# msq-dbw.net
KiCad netlist of a schematic drawn in EasyEDA Pro
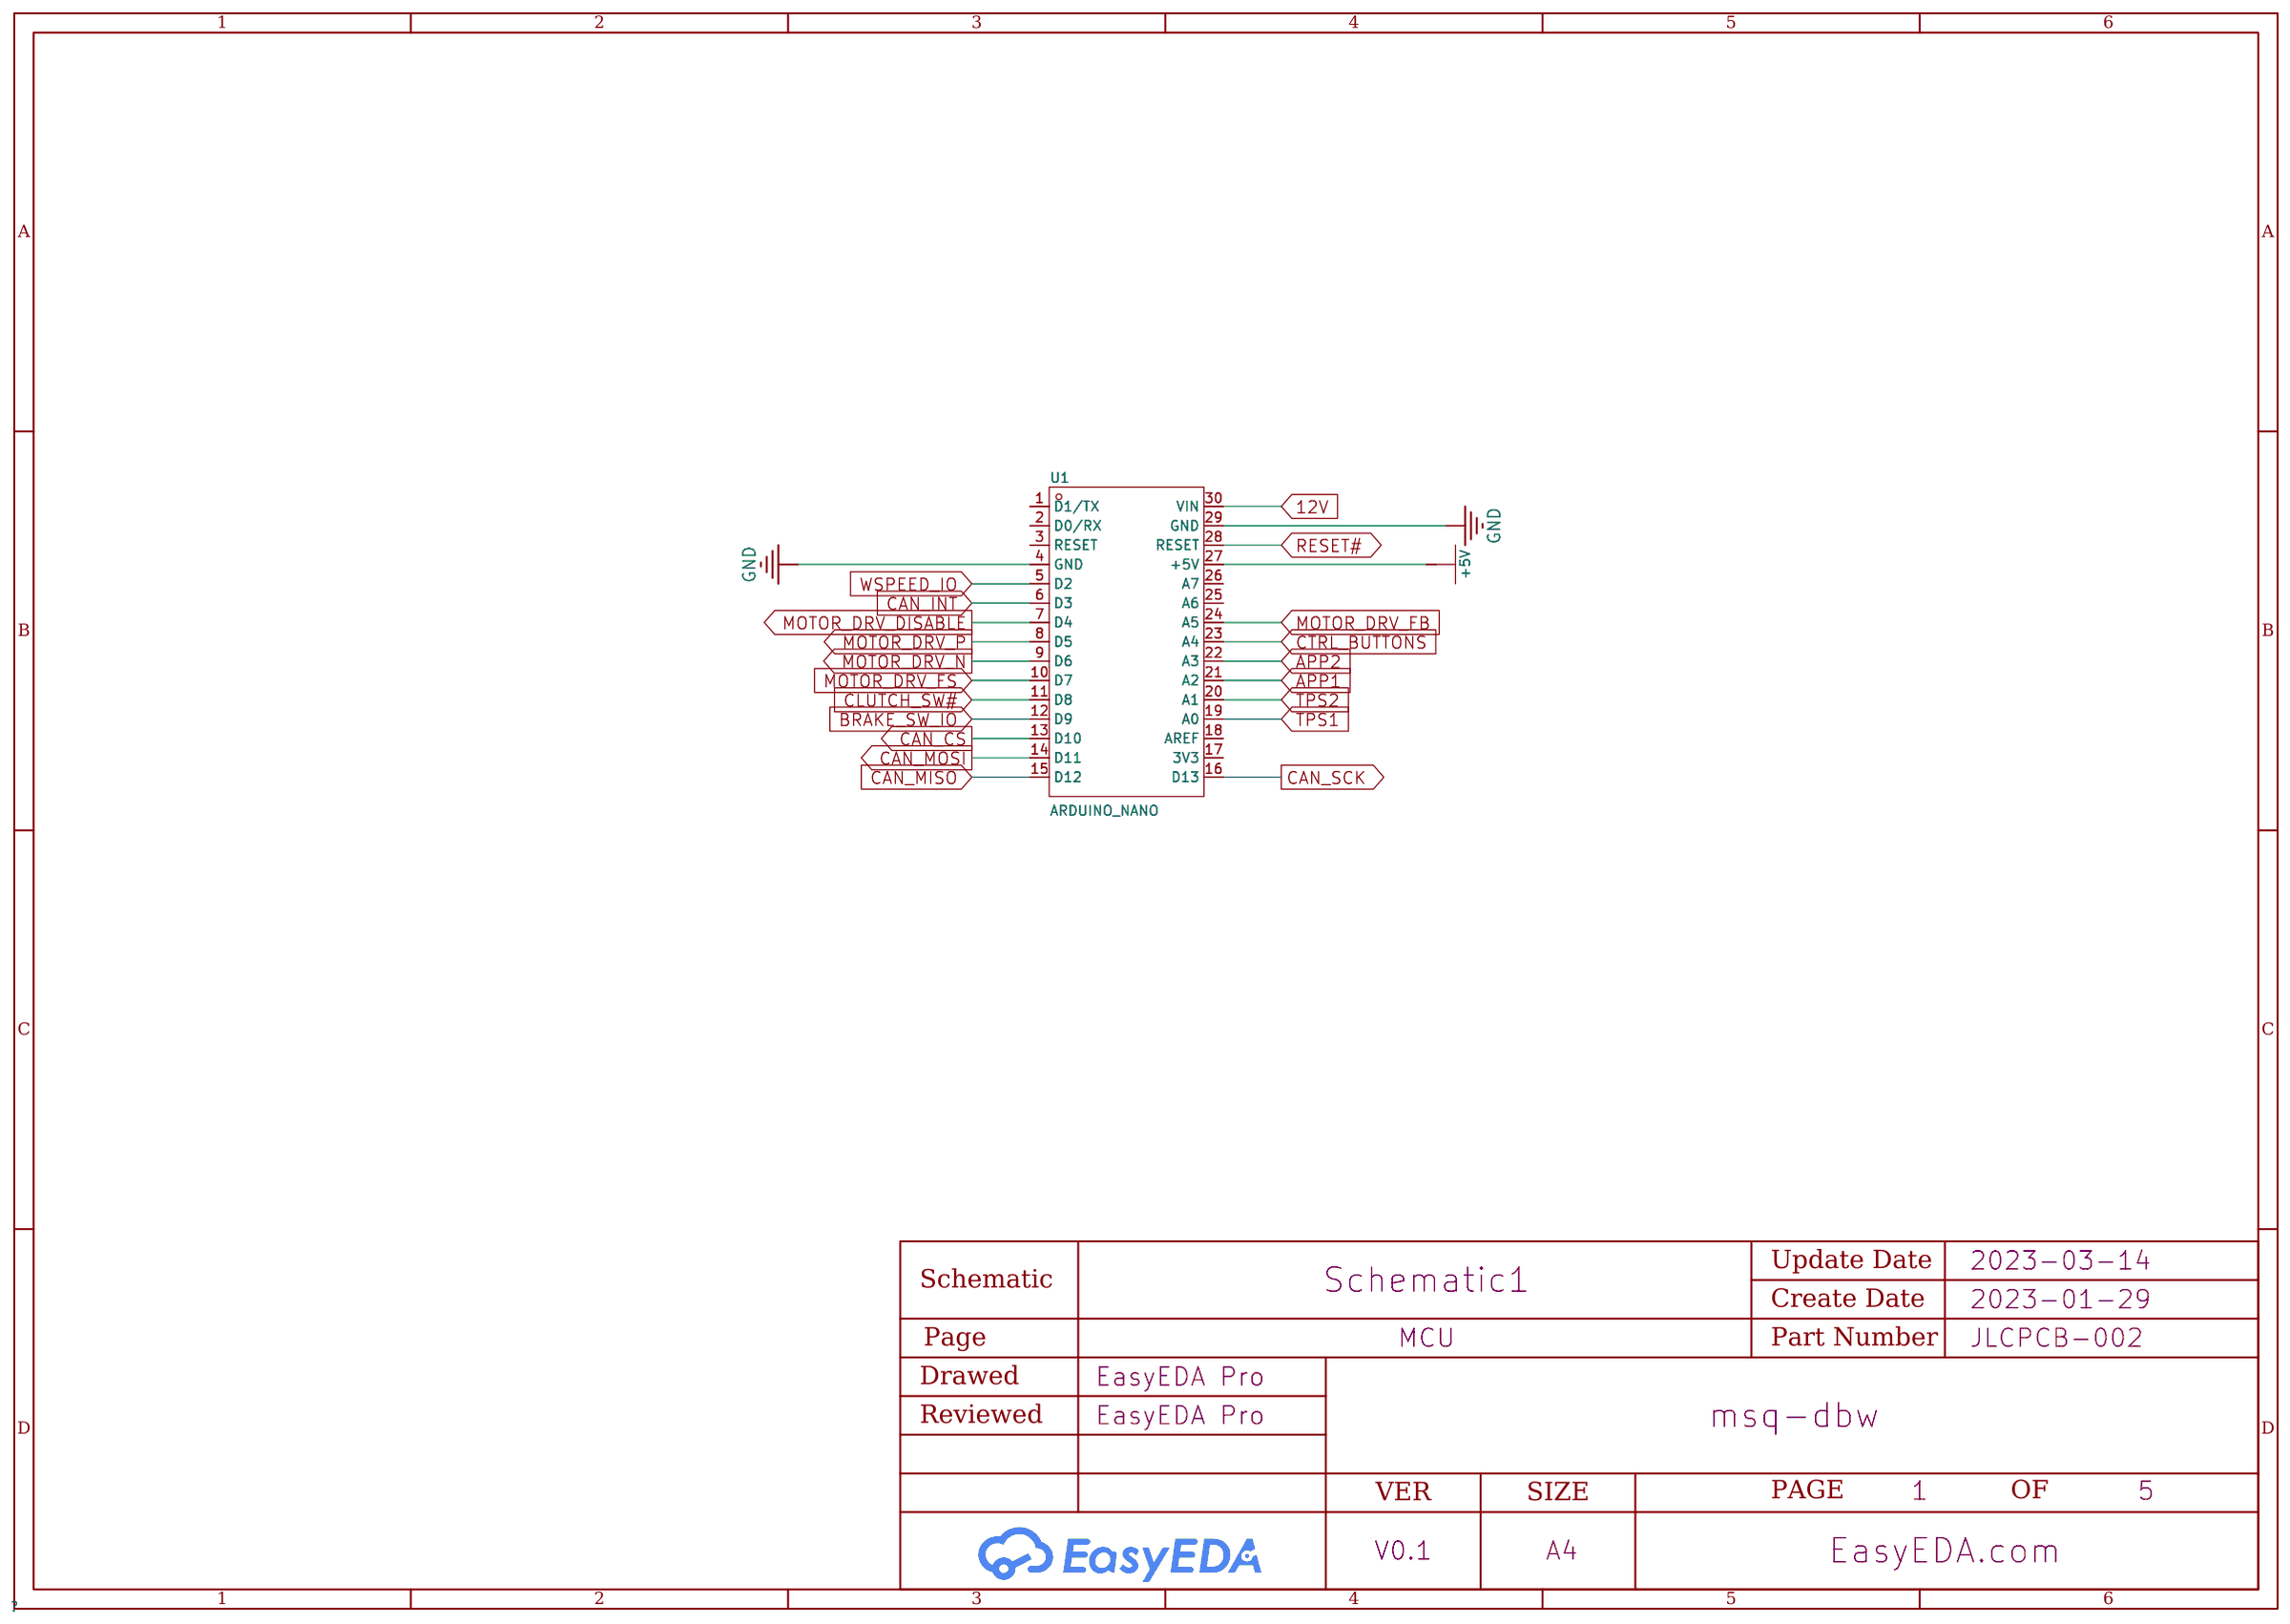
[diagram p0: MCU]
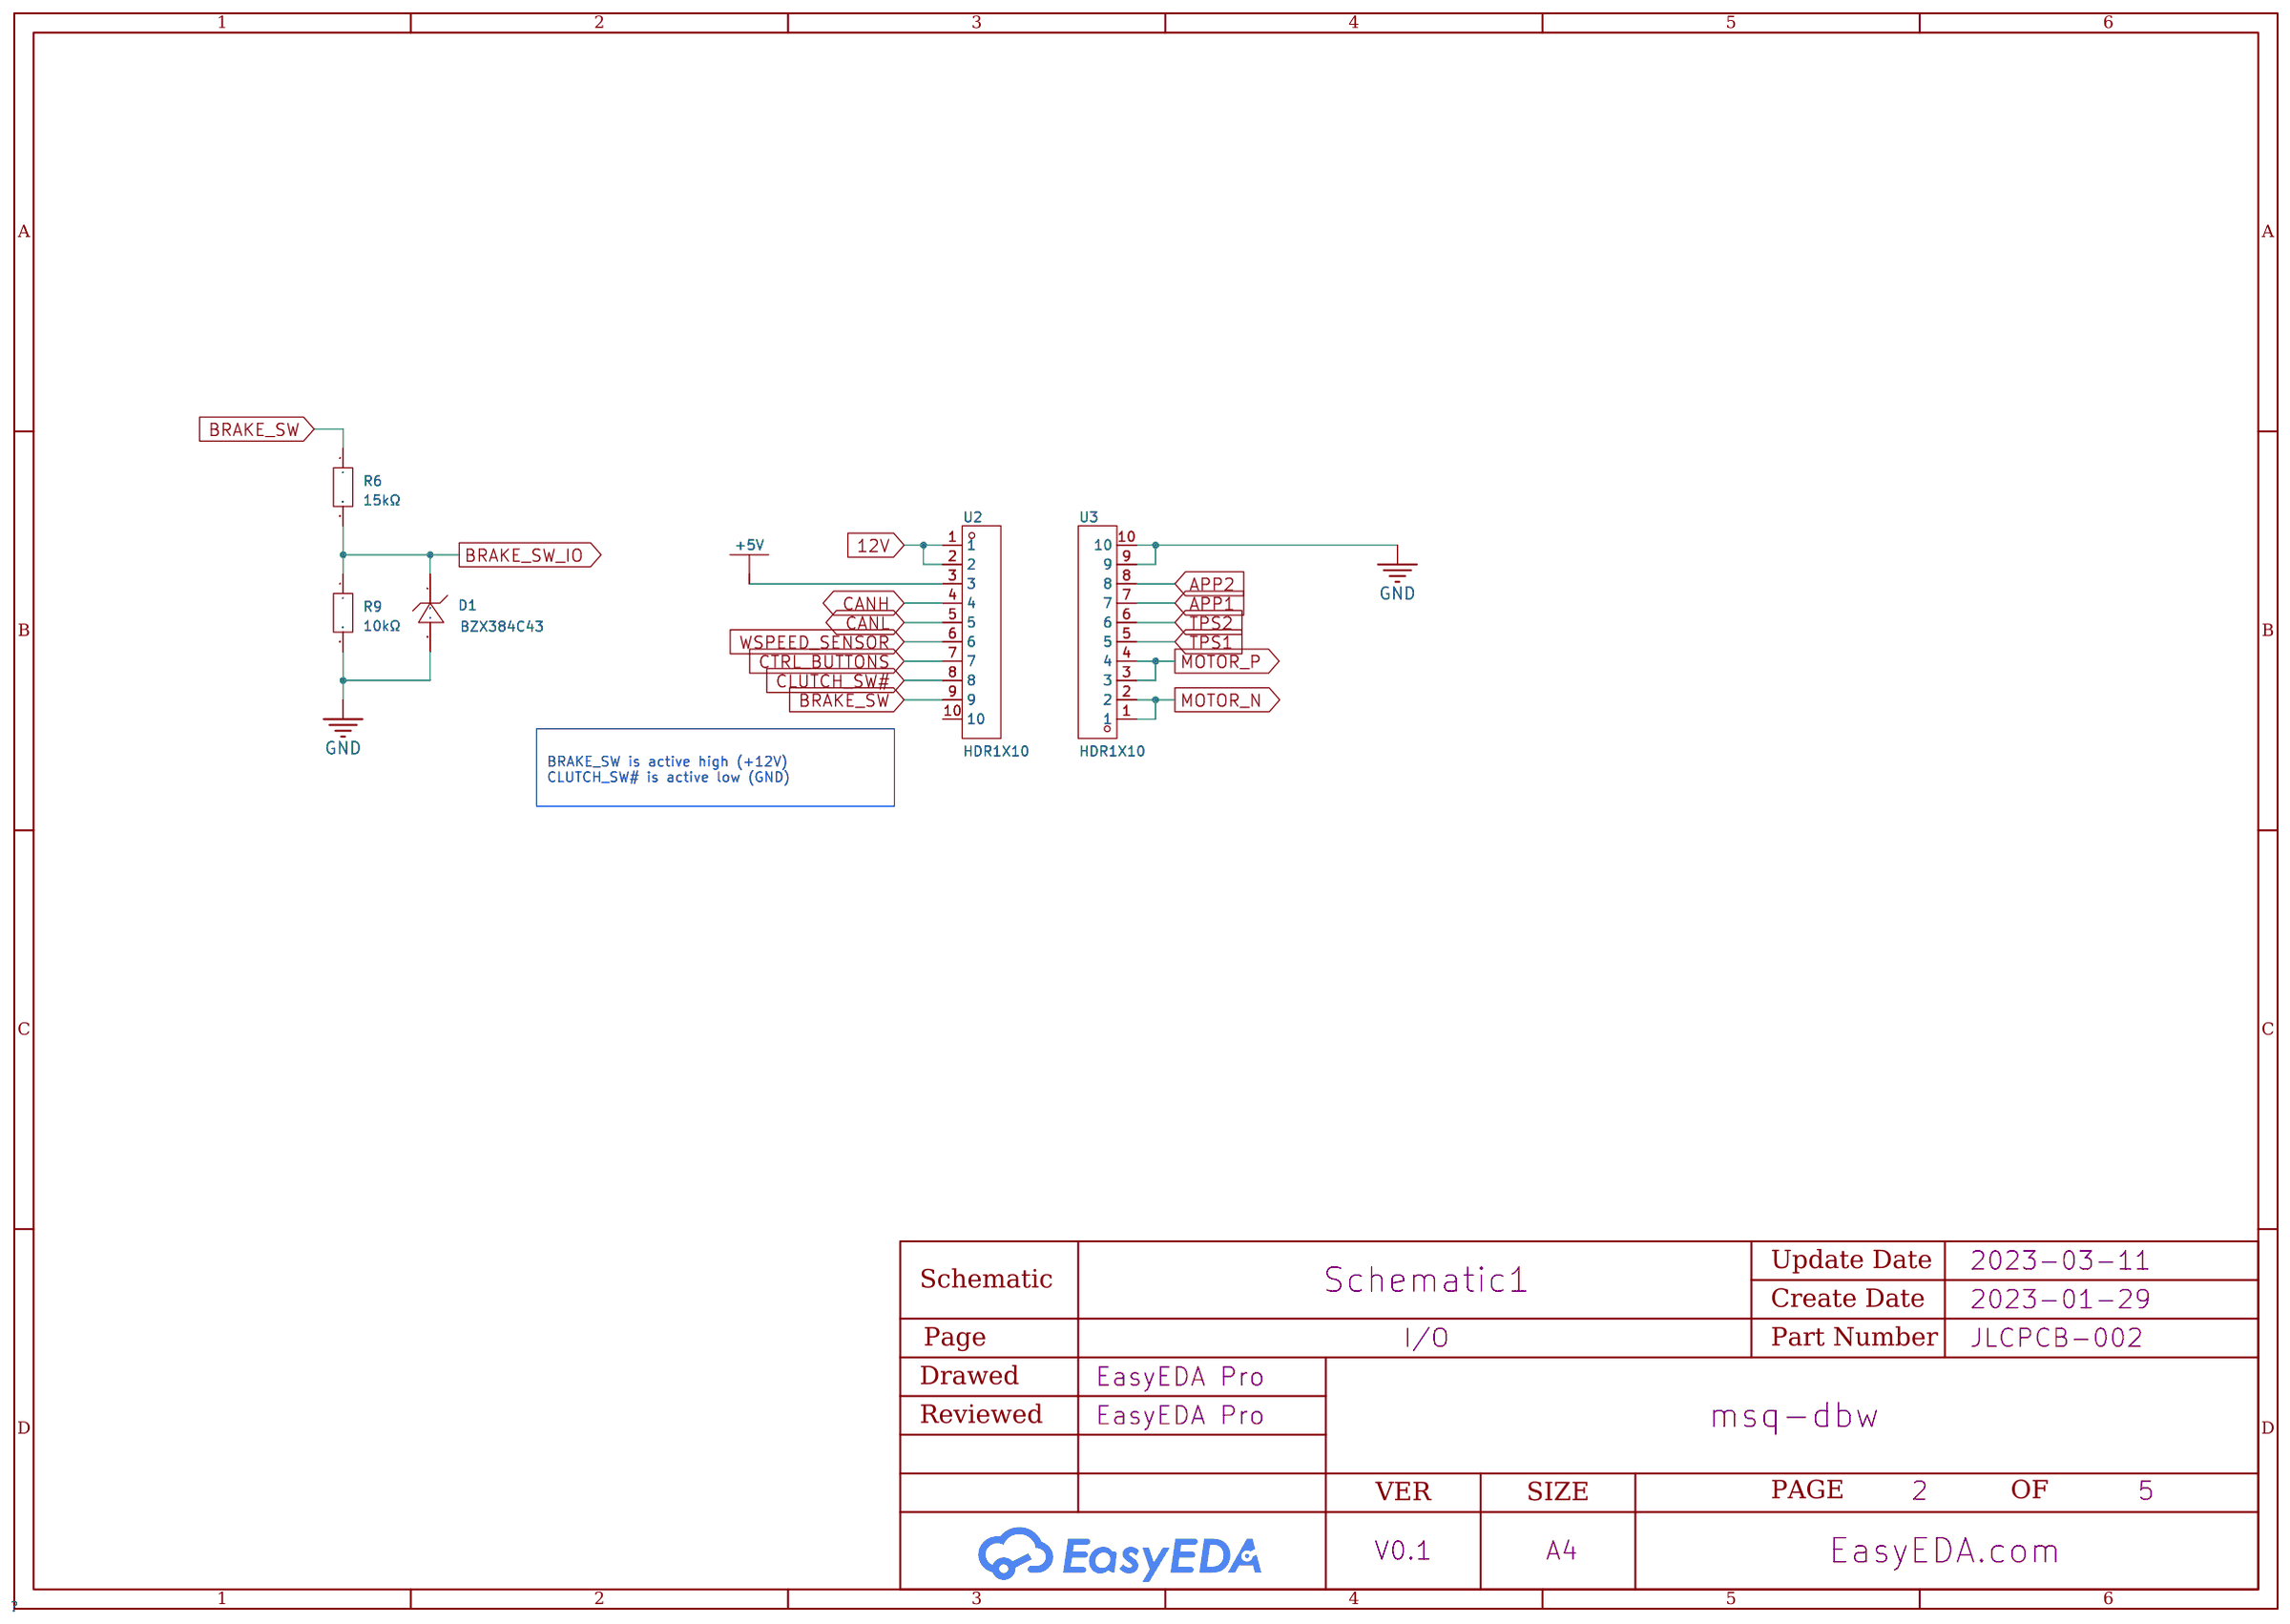
[diagram p1: I/O]
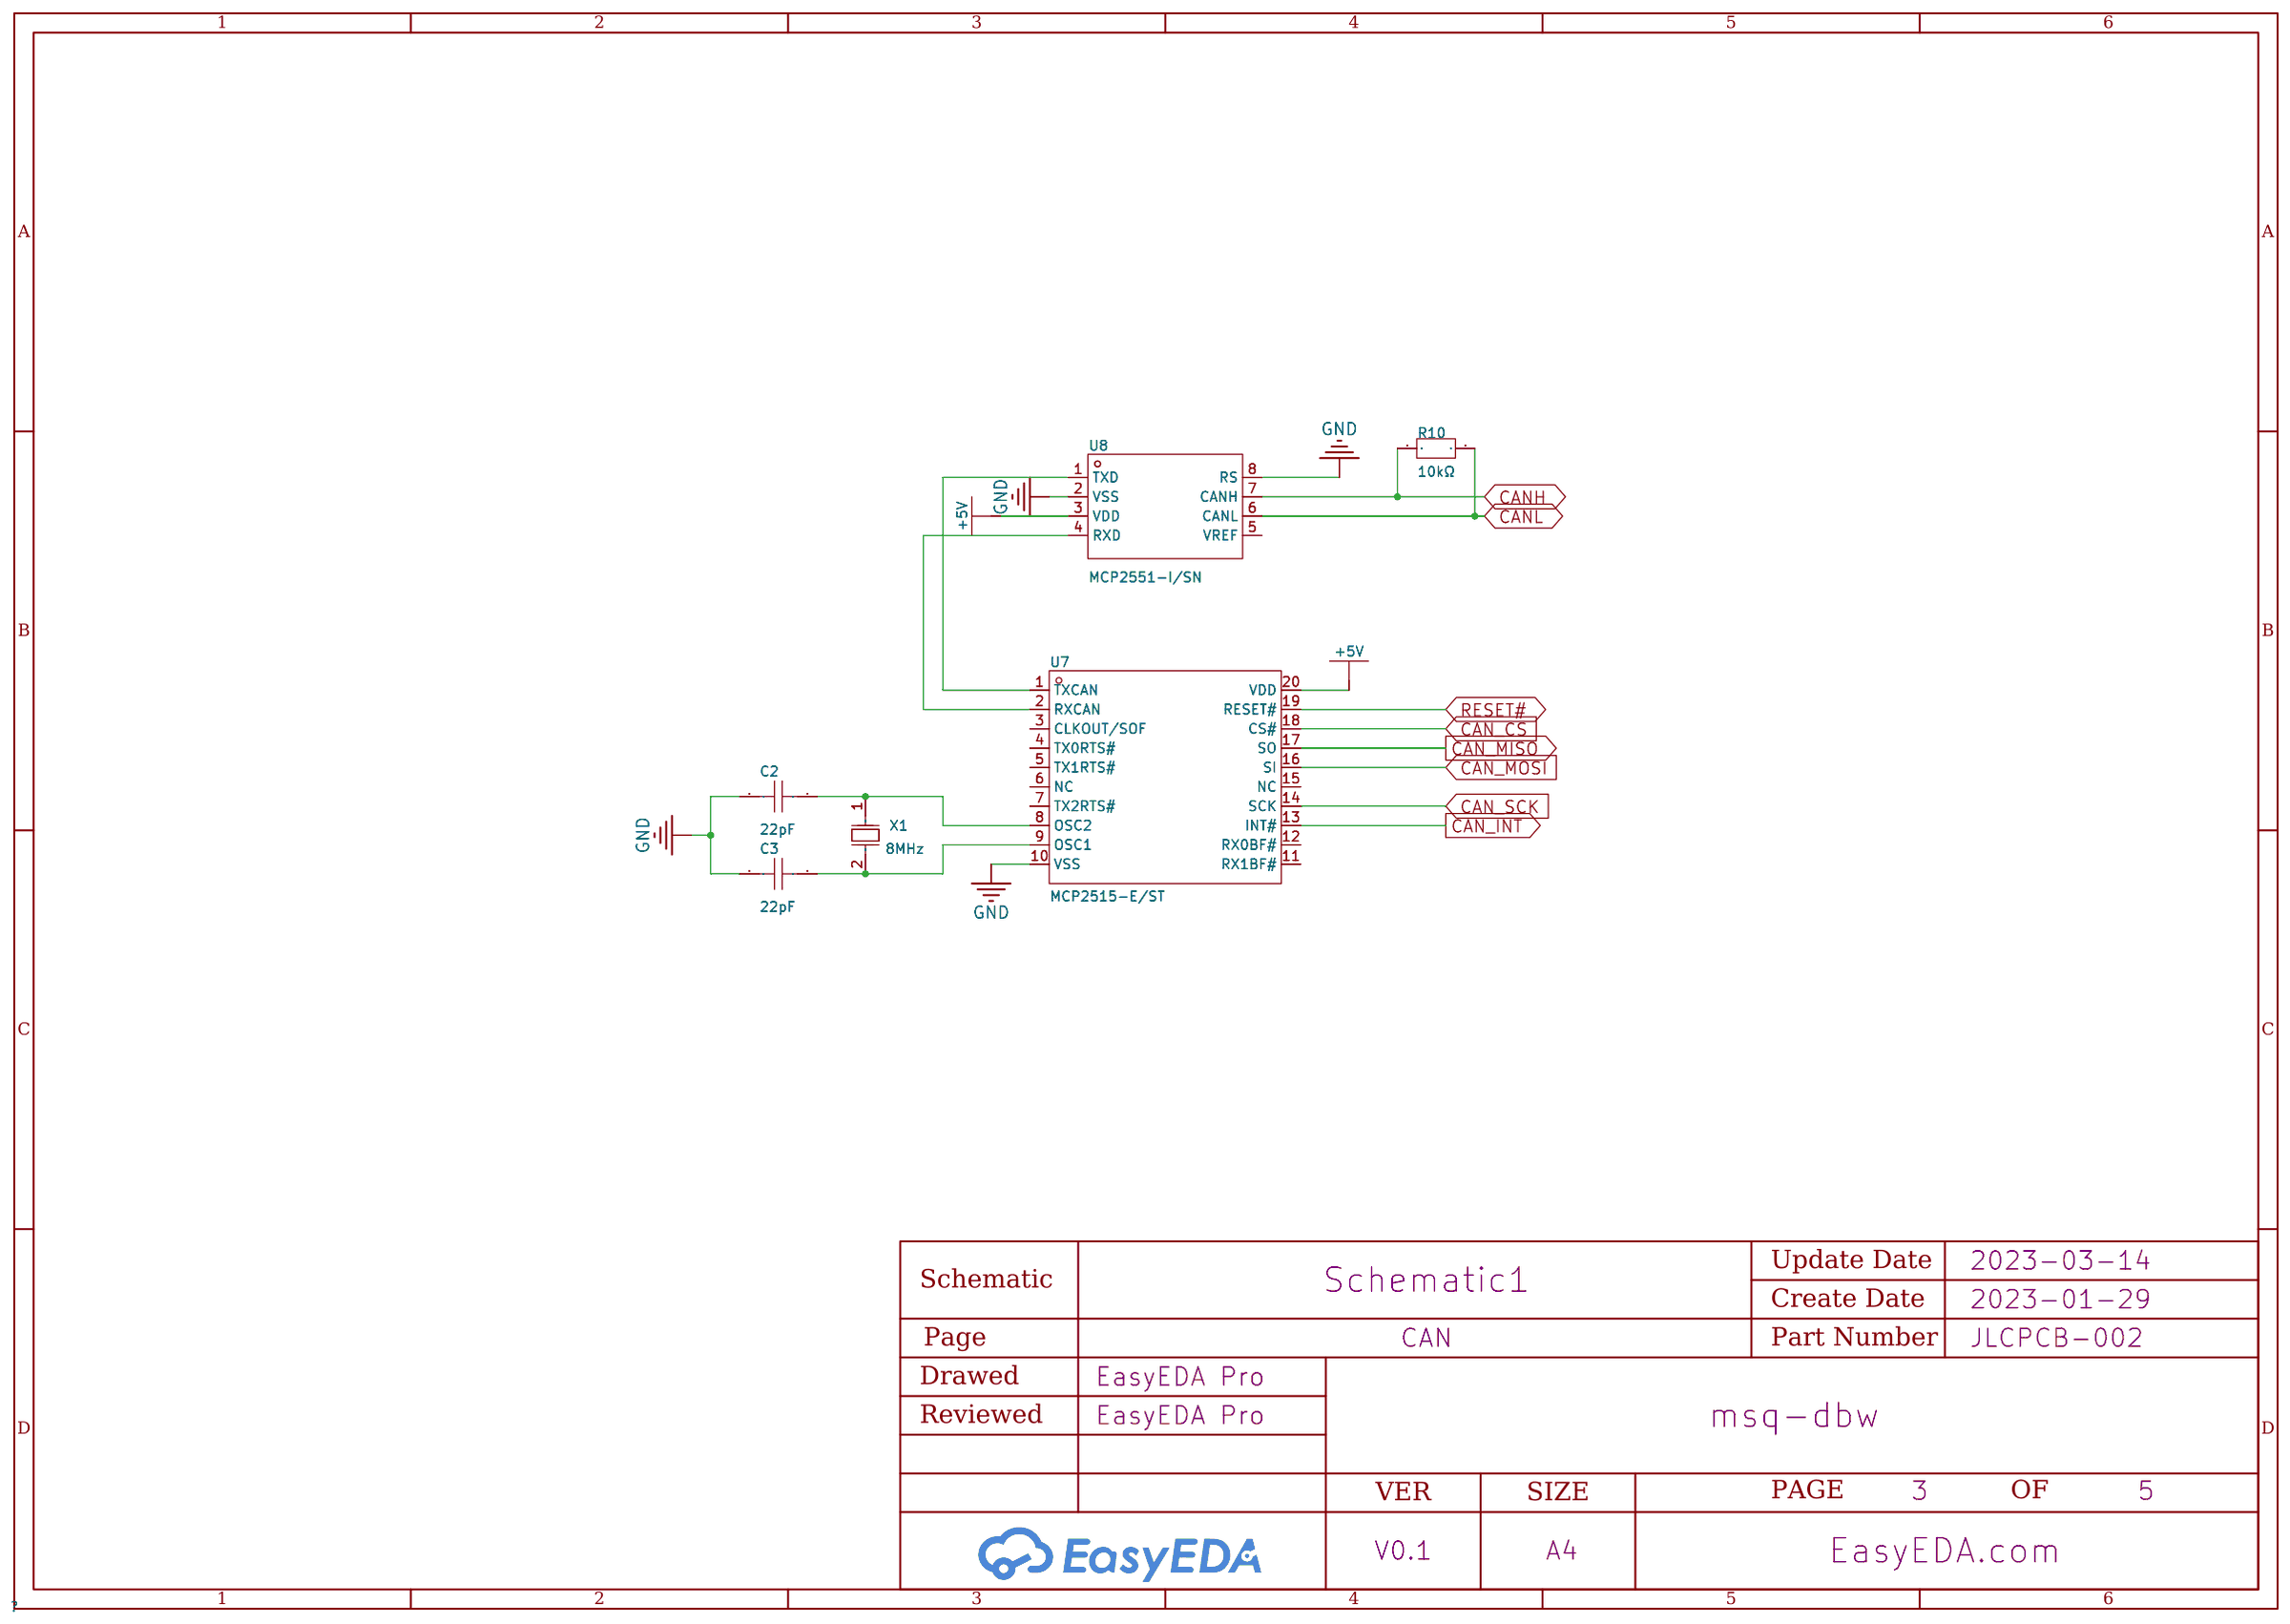
[diagram p2: CAN]
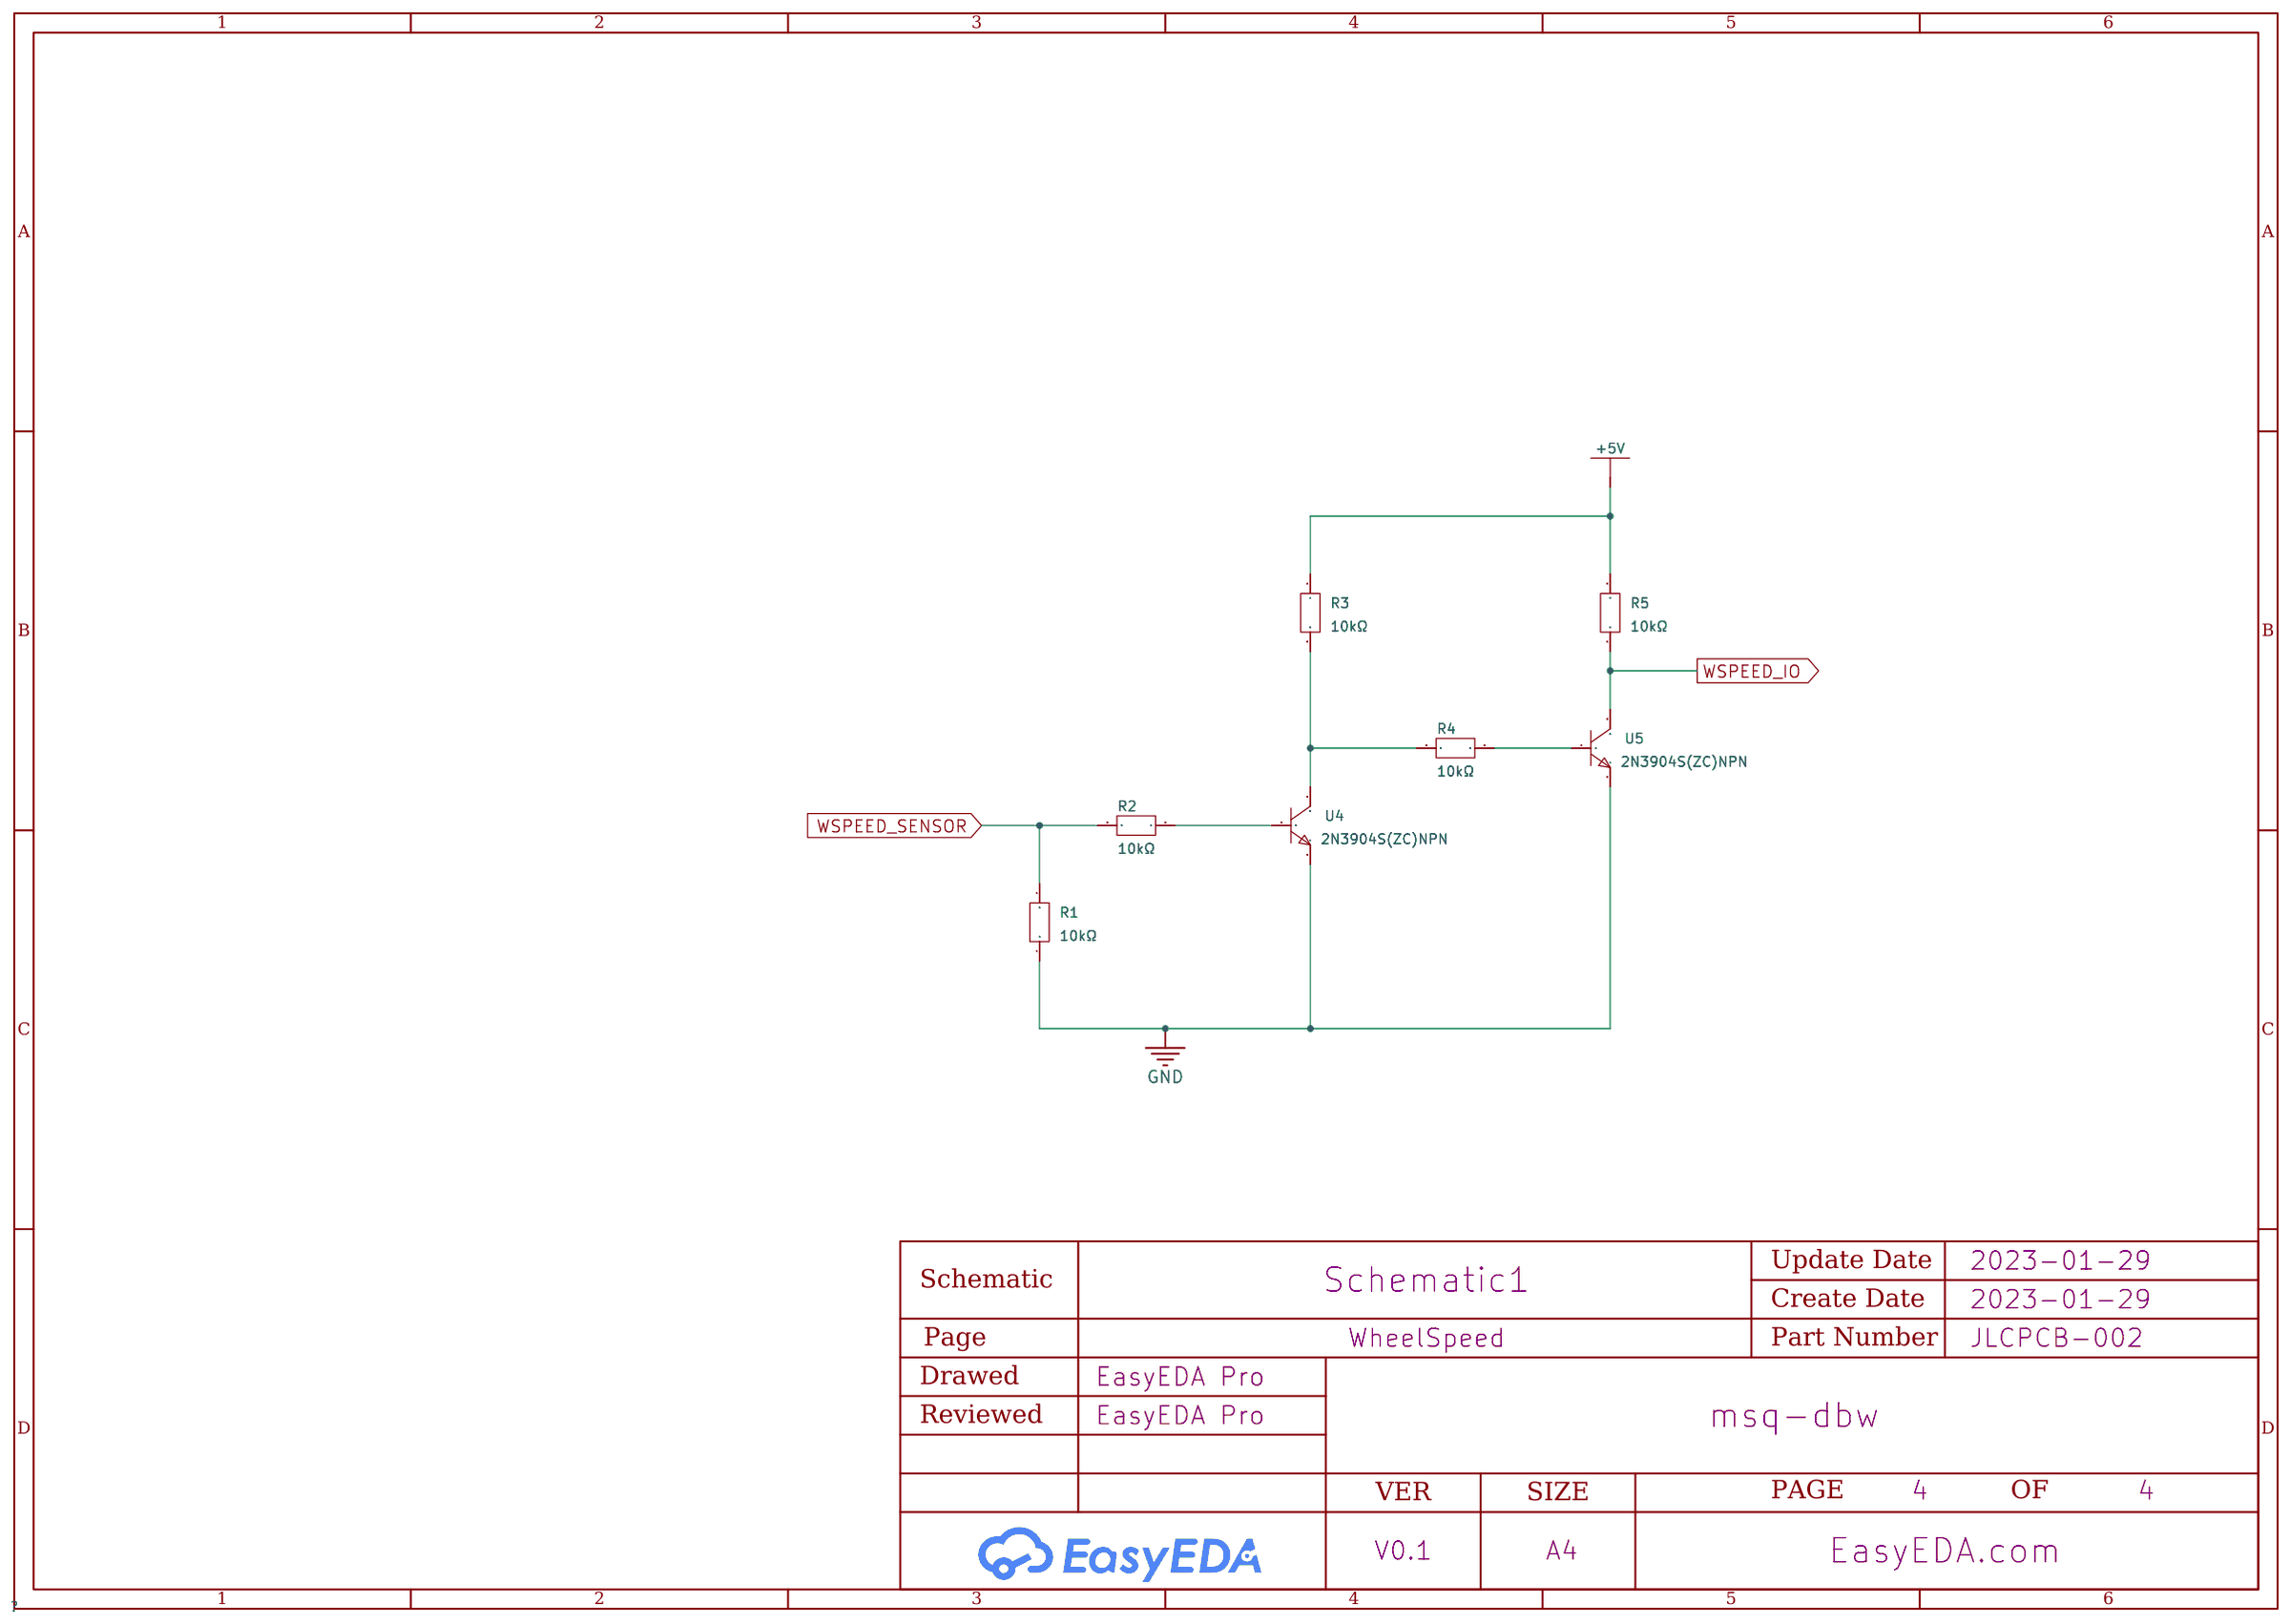
[diagram p3: WheelSpeed]
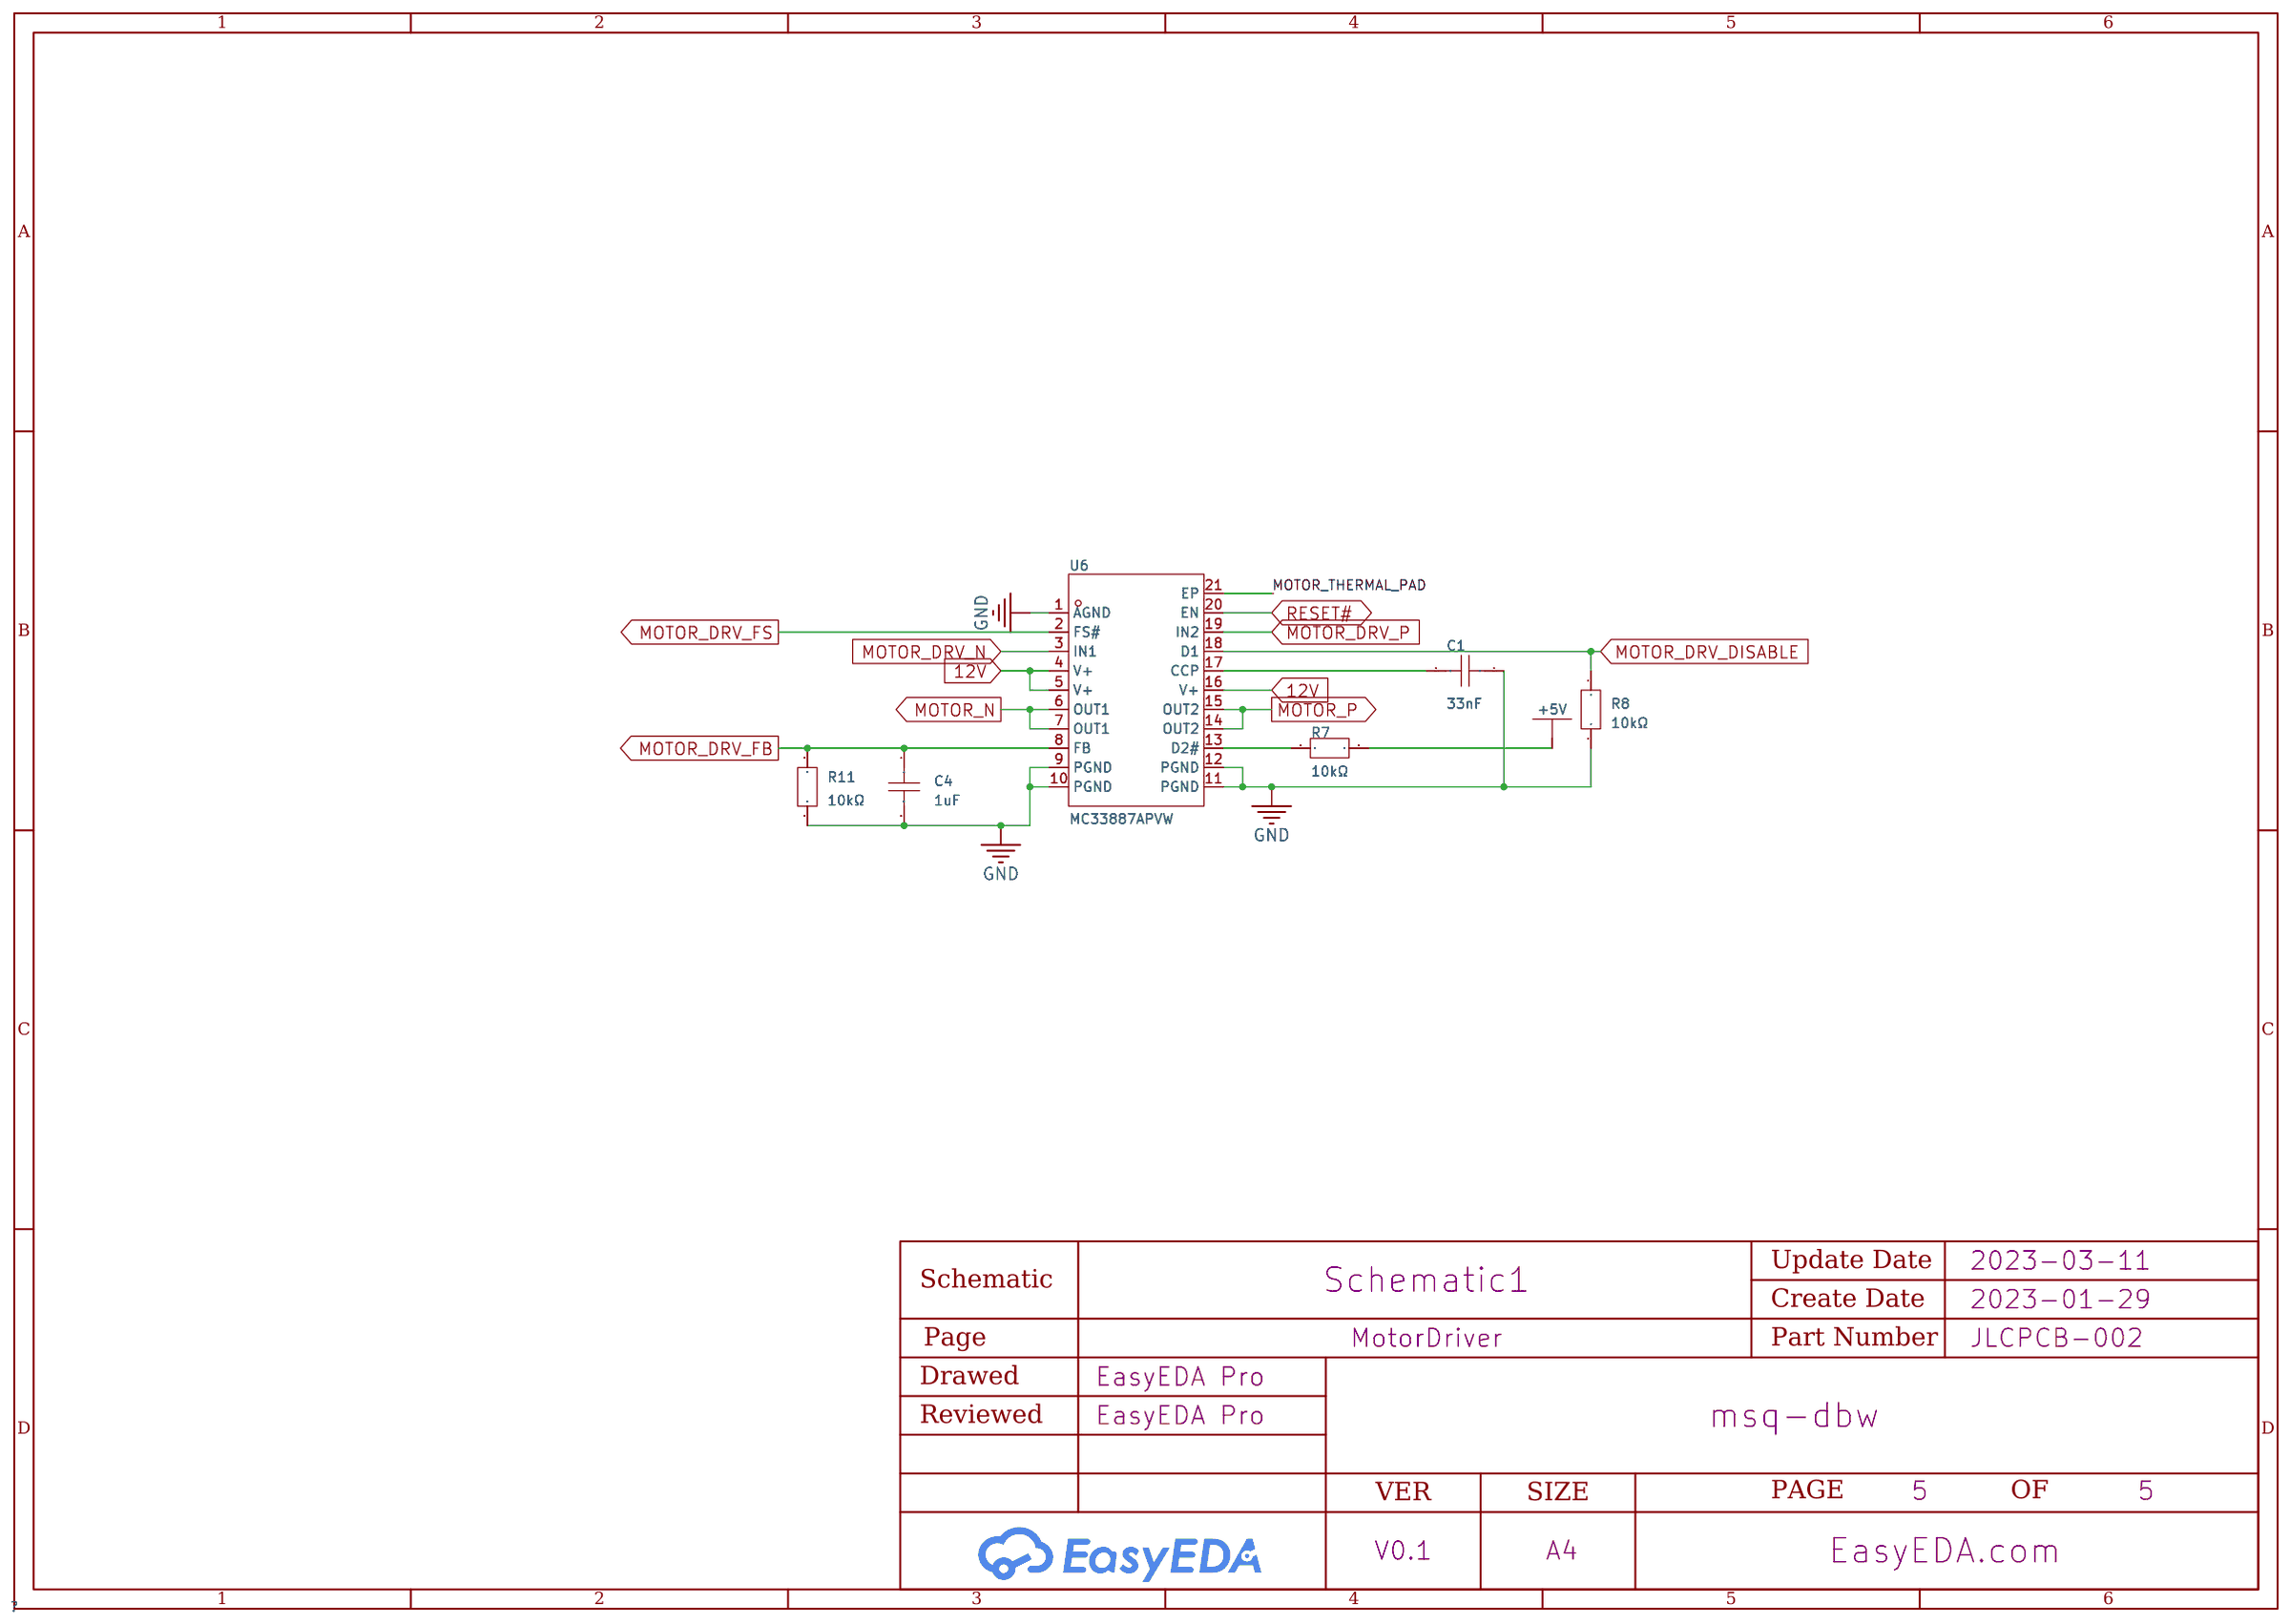
[diagram p4: MotorDriver]

(export (version "E")
  (design (tool "Eeschema 10.0.6"))
  (components
    (comp (ref "U1")
      (value "ARDUINO_NANO")
      (footprint "easyedapro:COMM-TH_ARDUINO_NANO")
      (libsource (lib "easyedapro") (part "ARDUINO_NANO"))
    )
    (comp (ref "D1")
      (value "BZX384C43")
      (footprint "easyedapro:SOD-323_L1.7-W1.3-LS2.6-RD")
      (fields (field (name "Manufacturer") "EIC") (field (name "Tolerance") "±2%"))
      (libsource (lib "easyedapro") (part "BZX384C43"))
    )
    (comp (ref "R6")
      (value "15kΩ")
      (footprint "easyedapro:R0805")
      (fields
        (field (name "Manufacturer Part") "0603WAF1002T5E")
        (field (name "Manufacturer") "UNI-ROYAL(厚声)")
        (field (name "Tolerance") "±1%")
      )
      (libsource (lib "easyedapro") (part "RT0805BRD07360RL"))
    )
    (comp (ref "R9")
      (value "10kΩ")
      (footprint "easyedapro:R0805")
      (fields
        (field (name "Manufacturer Part") "0603WAF1002T5E")
        (field (name "Manufacturer") "UNI-ROYAL(厚声)")
        (field (name "Tolerance") "±1%")
      )
      (libsource (lib "easyedapro") (part "RT0805BRD07360RL"))
    )
    (comp (ref "U2")
      (value "HDR1X10")
      (footprint "easyedapro:HDR-TH_10P-P2.54-V-F_C9900008052")
      (libsource (lib "easyedapro") (part "HDR1X10"))
    )
    (comp (ref "U3")
      (value "HDR1X10")
      (footprint "easyedapro:HDR-TH_10P-P2.54-V-F_C9900008052")
      (libsource (lib "easyedapro") (part "HDR1X10"))
    )
    (comp (ref "C2")
      (value "22pF")
      (footprint "easyedapro:C0603")
      (libsource (lib "easyedapro") (part "CAP"))
    )
    (comp (ref "C3")
      (value "22pF")
      (footprint "easyedapro:C0603")
      (libsource (lib "easyedapro") (part "CAP"))
    )
    (comp (ref "R10")
      (value "10kΩ")
      (footprint "easyedapro:R0805")
      (fields
        (field (name "Manufacturer Part") "0603WAF1002T5E")
        (field (name "Manufacturer") "UNI-ROYAL(厚声)")
        (field (name "Tolerance") "±1%")
      )
      (libsource (lib "easyedapro") (part "RT0805BRD07360RL"))
    )
    (comp (ref "U7")
      (value "MCP2515-E/ST")
      (footprint "easyedapro:TSSOP-20_L6.5-W4.4-P0.65-LS6.4-BL")
      (fields (field (name "Manufacturer") "MICROCHIP(美国微芯)"))
      (libsource (lib "easyedapro") (part "MCP2515-E/ST"))
    )
    (comp (ref "U8")
      (value "MCP2551-I/SN")
      (footprint "easyedapro:SOIC-8_L4.9-W3.9-P1.27-LS6.0-BL")
      (description "Type:Transceiver Supply Voltage:4.5V~5.5V Supply Voltage:4.5V~5.5V")
      (fields (field (name "Manufacturer") "MICROCHIP(美国微芯)"))
      (libsource (lib "easyedapro") (part "MCP2551-I/SN"))
    )
    (comp (ref "X1")
      (value "8MHz")
      (footprint "easyedapro:CRYSTAL-TH_L10.8-W4.5-P4.88")
      (fields (field (name "Manufacturer Part") "ATS08A") (field (name "Manufacturer") "CTS(西迪斯)"))
      (libsource (lib "easyedapro") (part "ATS08A"))
    )
    (comp (ref "R1")
      (value "10kΩ")
      (footprint "easyedapro:R0805")
      (fields
        (field (name "Manufacturer Part") "0603WAF1002T5E")
        (field (name "Manufacturer") "UNI-ROYAL(厚声)")
        (field (name "Tolerance") "±1%")
      )
      (libsource (lib "easyedapro") (part "RT0805BRD07360RL"))
    )
    (comp (ref "R2")
      (value "10kΩ")
      (footprint "easyedapro:R0805")
      (fields
        (field (name "Manufacturer Part") "0603WAF1002T5E")
        (field (name "Manufacturer") "UNI-ROYAL(厚声)")
        (field (name "Tolerance") "±1%")
      )
      (libsource (lib "easyedapro") (part "RT0805BRD07360RL"))
    )
    (comp (ref "R3")
      (value "10kΩ")
      (footprint "easyedapro:R0805")
      (fields
        (field (name "Manufacturer Part") "0603WAF1002T5E")
        (field (name "Manufacturer") "UNI-ROYAL(厚声)")
        (field (name "Tolerance") "±1%")
      )
      (libsource (lib "easyedapro") (part "RT0805BRD07360RL"))
    )
    (comp (ref "R4")
      (value "10kΩ")
      (footprint "easyedapro:R0805")
      (fields
        (field (name "Manufacturer Part") "0603WAF1002T5E")
        (field (name "Manufacturer") "UNI-ROYAL(厚声)")
        (field (name "Tolerance") "±1%")
      )
      (libsource (lib "easyedapro") (part "RT0805BRD07360RL"))
    )
    (comp (ref "R5")
      (value "10kΩ")
      (footprint "easyedapro:R0805")
      (fields
        (field (name "Manufacturer Part") "0603WAF1002T5E")
        (field (name "Manufacturer") "UNI-ROYAL(厚声)")
        (field (name "Tolerance") "±1%")
      )
      (libsource (lib "easyedapro") (part "RT0805BRD07360RL"))
    )
    (comp (ref "U4")
      (value "2N3904S(ZC)NPN")
      (footprint "easyedapro:SOT-23-3_L2.9-W1.3-P0.95-LS2.4-BR")
      (libsource (lib "easyedapro") (part "2N3904S(ZC)NPN"))
    )
    (comp (ref "U5")
      (value "2N3904S(ZC)NPN")
      (footprint "easyedapro:SOT-23-3_L2.9-W1.3-P0.95-LS2.4-BR")
      (libsource (lib "easyedapro") (part "2N3904S(ZC)NPN"))
    )
    (comp (ref "C1")
      (value "33nF")
      (footprint "easyedapro:C0603")
      (libsource (lib "easyedapro") (part "CAP"))
    )
    (comp (ref "C4") (value "1uF") (footprint "easyedapro:C0603") (libsource (lib "easyedapro") (part "CAP")))
    (comp (ref "R7")
      (value "10kΩ")
      (footprint "easyedapro:R0805")
      (fields
        (field (name "Manufacturer Part") "0603WAF1002T5E")
        (field (name "Manufacturer") "UNI-ROYAL(厚声)")
        (field (name "Tolerance") "±1%")
      )
      (libsource (lib "easyedapro") (part "RT0805BRD07360RL"))
    )
    (comp (ref "R8")
      (value "10kΩ")
      (footprint "easyedapro:R0805")
      (fields
        (field (name "Manufacturer Part") "0603WAF1002T5E")
        (field (name "Manufacturer") "UNI-ROYAL(厚声)")
        (field (name "Tolerance") "±1%")
      )
      (libsource (lib "easyedapro") (part "RT0805BRD07360RL"))
    )
    (comp (ref "R11")
      (value "10kΩ")
      (footprint "easyedapro:R0805")
      (fields
        (field (name "Manufacturer Part") "0603WAF1002T5E")
        (field (name "Manufacturer") "UNI-ROYAL(厚声)")
        (field (name "Tolerance") "±1%")
      )
      (libsource (lib "easyedapro") (part "RT0805BRD07360RL"))
    )
    (comp (ref "U6")
      (value "MC33887APVW")
      (footprint "easyedapro:HSOP-20_L15.9-W11.0-P1.27-LS14.2-TL-EP")
      (fields (field (name "Manufacturer") "NXP(恩智浦)"))
      (libsource (lib "easyedapro") (part "MC33887APVW"))
    )
  )
  (nets
    (net (code "1") (name "+5V") (class "Default")
      (node (ref "R3") (pin "1") (pinfunction "1_1") (pintype "input"))
      (node (ref "R5") (pin "2") (pinfunction "2_2") (pintype "input"))
      (node (ref "R7") (pin "1") (pinfunction "1_1") (pintype "input"))
      (node (ref "U1") (pin "27") (pinfunction "+5V_27") (pintype "input"))
      (node (ref "U2") (pin "3") (pinfunction "3_3") (pintype "input"))
      (node (ref "U7") (pin "20") (pinfunction "VDD_20") (pintype "input"))
      (node (ref "U8") (pin "3") (pinfunction "VDD_3") (pintype "input"))
    )
    (net (code "2") (name "12V") (class "Default")
      (node (ref "U1") (pin "30") (pinfunction "VIN_30") (pintype "input"))
      (node (ref "U2") (pin "1") (pinfunction "1_1") (pintype "input"))
      (node (ref "U2") (pin "2") (pinfunction "2_2") (pintype "input"))
      (node (ref "U6") (pin "16") (pinfunction "V+_16") (pintype "input"))
      (node (ref "U6") (pin "4") (pinfunction "V+_4") (pintype "input"))
      (node (ref "U6") (pin "5") (pinfunction "V+_5") (pintype "input"))
    )
    (net (code "3") (name "APP1") (class "Default")
      (node (ref "U1") (pin "21") (pinfunction "A2_21") (pintype "input"))
      (node (ref "U3") (pin "7") (pinfunction "7_7") (pintype "input"))
    )
    (net (code "4") (name "APP2") (class "Default")
      (node (ref "U1") (pin "22") (pinfunction "A3_22") (pintype "input"))
      (node (ref "U3") (pin "8") (pinfunction "8_8") (pintype "input"))
    )
    (net (code "5") (name "BRAKE_SW") (class "Default")
      (node (ref "R6") (pin "1") (pinfunction "1_1") (pintype "input"))
      (node (ref "U2") (pin "9") (pinfunction "9_9") (pintype "input"))
    )
    (net (code "6") (name "BRAKE_SW_IO") (class "Default")
      (node (ref "D1") (pin "1") (pinfunction "C_1") (pintype "input"))
      (node (ref "R6") (pin "2") (pinfunction "2_2") (pintype "input"))
      (node (ref "R9") (pin "1") (pinfunction "1_1") (pintype "input"))
      (node (ref "U1") (pin "12") (pinfunction "D9_12") (pintype "input"))
    )
    (net (code "7") (name "CANH") (class "Default")
      (node (ref "R10") (pin "1") (pinfunction "1_1") (pintype "input"))
      (node (ref "U2") (pin "4") (pinfunction "4_4") (pintype "input"))
      (node (ref "U8") (pin "7") (pinfunction "CANH_7") (pintype "input"))
    )
    (net (code "8") (name "CANL") (class "Default")
      (node (ref "R10") (pin "2") (pinfunction "2_2") (pintype "input"))
      (node (ref "U2") (pin "5") (pinfunction "5_5") (pintype "input"))
      (node (ref "U8") (pin "6") (pinfunction "CANL_6") (pintype "input"))
    )
    (net (code "9") (name "CAN_CS") (class "Default")
      (node (ref "U1") (pin "13") (pinfunction "D10_13") (pintype "input"))
      (node (ref "U7") (pin "18") (pinfunction "CS#_18") (pintype "input"))
    )
    (net (code "10") (name "CAN_INT") (class "Default")
      (node (ref "U1") (pin "6") (pinfunction "D3_6") (pintype "input"))
      (node (ref "U7") (pin "13") (pinfunction "INT#_13") (pintype "input"))
    )
    (net (code "11") (name "CAN_MISO") (class "Default")
      (node (ref "U1") (pin "15") (pinfunction "D12_15") (pintype "input"))
      (node (ref "U7") (pin "17") (pinfunction "SO_17") (pintype "input"))
    )
    (net (code "12") (name "CAN_MOSI") (class "Default")
      (node (ref "U1") (pin "14") (pinfunction "D11_14") (pintype "input"))
      (node (ref "U7") (pin "16") (pinfunction "SI_16") (pintype "input"))
    )
    (net (code "13") (name "CAN_SCK") (class "Default")
      (node (ref "U1") (pin "16") (pinfunction "D13_16") (pintype "input"))
      (node (ref "U7") (pin "14") (pinfunction "SCK_14") (pintype "input"))
    )
    (net (code "14") (name "CLUTCH_SW#") (class "Default")
      (node (ref "U1") (pin "11") (pinfunction "D8_11") (pintype "input"))
      (node (ref "U2") (pin "8") (pinfunction "8_8") (pintype "input"))
    )
    (net (code "15") (name "CTRL_BUTTONS") (class "Default")
      (node (ref "U1") (pin "23") (pinfunction "A4_23") (pintype "input"))
      (node (ref "U2") (pin "7") (pinfunction "7_7") (pintype "input"))
    )
    (net (code "16") (name "GND") (class "Default")
      (node (ref "C1") (pin "1") (pinfunction "1_1") (pintype "input"))
      (node (ref "C2") (pin "2") (pinfunction "2_2") (pintype "input"))
      (node (ref "C3") (pin "2") (pinfunction "2_2") (pintype "input"))
      (node (ref "C4") (pin "2") (pinfunction "2_2") (pintype "input"))
      (node (ref "D1") (pin "2") (pinfunction "A_2") (pintype "input"))
      (node (ref "R1") (pin "1") (pinfunction "1_1") (pintype "input"))
      (node (ref "R11") (pin "1") (pinfunction "1_1") (pintype "input"))
      (node (ref "R8") (pin "2") (pinfunction "2_2") (pintype "input"))
      (node (ref "R9") (pin "2") (pinfunction "2_2") (pintype "input"))
      (node (ref "U1") (pin "29") (pinfunction "GND_29") (pintype "input"))
      (node (ref "U1") (pin "4") (pinfunction "GND_4") (pintype "input"))
      (node (ref "U3") (pin "10") (pinfunction "10_10") (pintype "input"))
      (node (ref "U3") (pin "9") (pinfunction "9_9") (pintype "input"))
      (node (ref "U4") (pin "2") (pinfunction "E_2") (pintype "input"))
      (node (ref "U5") (pin "2") (pinfunction "E_2") (pintype "input"))
      (node (ref "U6") (pin "1") (pinfunction "AGND_1") (pintype "input"))
      (node (ref "U6") (pin "10") (pinfunction "PGND_10") (pintype "input"))
      (node (ref "U6") (pin "11") (pinfunction "PGND_11") (pintype "input"))
      (node (ref "U6") (pin "12") (pinfunction "PGND_12") (pintype "input"))
      (node (ref "U6") (pin "9") (pinfunction "PGND_9") (pintype "input"))
      (node (ref "U7") (pin "10") (pinfunction "VSS_10") (pintype "input"))
      (node (ref "U8") (pin "2") (pinfunction "VSS_2") (pintype "input"))
      (node (ref "U8") (pin "8") (pinfunction "RS_8") (pintype "input"))
    )
    (net (code "17") (name "MOTOR_DRV_DISABLE") (class "Default")
      (node (ref "R8") (pin "1") (pinfunction "1_1") (pintype "input"))
      (node (ref "U1") (pin "7") (pinfunction "D4_7") (pintype "input"))
      (node (ref "U6") (pin "18") (pinfunction "D1_18") (pintype "input"))
    )
    (net (code "18") (name "MOTOR_DRV_FB") (class "Default")
      (node (ref "C4") (pin "1") (pinfunction "1_1") (pintype "input"))
      (node (ref "R11") (pin "2") (pinfunction "2_2") (pintype "input"))
      (node (ref "U1") (pin "24") (pinfunction "A5_24") (pintype "input"))
      (node (ref "U6") (pin "8") (pinfunction "FB_8") (pintype "input"))
    )
    (net (code "19") (name "MOTOR_DRV_FS") (class "Default")
      (node (ref "U1") (pin "10") (pinfunction "D7_10") (pintype "input"))
      (node (ref "U6") (pin "2") (pinfunction "FS#_2") (pintype "input"))
    )
    (net (code "20") (name "MOTOR_DRV_N") (class "Default")
      (node (ref "U1") (pin "9") (pinfunction "D6_9") (pintype "input"))
      (node (ref "U6") (pin "3") (pinfunction "IN1_3") (pintype "input"))
    )
    (net (code "21") (name "MOTOR_DRV_P") (class "Default")
      (node (ref "U1") (pin "8") (pinfunction "D5_8") (pintype "input"))
      (node (ref "U6") (pin "19") (pinfunction "IN2_19") (pintype "input"))
    )
    (net (code "22") (name "MOTOR_N") (class "Default")
      (node (ref "U3") (pin "1") (pinfunction "1_1") (pintype "input"))
      (node (ref "U3") (pin "2") (pinfunction "2_2") (pintype "input"))
      (node (ref "U6") (pin "6") (pinfunction "OUT1_6") (pintype "input"))
      (node (ref "U6") (pin "7") (pinfunction "OUT1_7") (pintype "input"))
    )
    (net (code "23") (name "MOTOR_P") (class "Default")
      (node (ref "U3") (pin "3") (pinfunction "3_3") (pintype "input"))
      (node (ref "U3") (pin "4") (pinfunction "4_4") (pintype "input"))
      (node (ref "U6") (pin "14") (pinfunction "OUT2_14") (pintype "input"))
      (node (ref "U6") (pin "15") (pinfunction "OUT2_15") (pintype "input"))
    )
    (net (code "24") (name "MOTOR_THERMAL_PAD") (class "Default")
      (node (ref "U6") (pin "21") (pinfunction "EP_21") (pintype "input"))
    )
    (net (code "25") (name "Net-(U4-B)") (class "Default")
      (node (ref "R2") (pin "1") (pinfunction "1_1") (pintype "input"))
      (node (ref "U4") (pin "1") (pinfunction "B_1") (pintype "input"))
    )
    (net (code "26") (name "Net-(U4-C)") (class "Default")
      (node (ref "R3") (pin "2") (pinfunction "2_2") (pintype "input"))
      (node (ref "R4") (pin "1") (pinfunction "1_1") (pintype "input"))
      (node (ref "U4") (pin "3") (pinfunction "C_3") (pintype "input"))
    )
    (net (code "27") (name "Net-(U5-B)") (class "Default")
      (node (ref "R4") (pin "2") (pinfunction "2_2") (pintype "input"))
      (node (ref "U5") (pin "1") (pinfunction "B_1") (pintype "input"))
    )
    (net (code "28") (name "Net-(U6-CCP)") (class "Default")
      (node (ref "C1") (pin "2") (pinfunction "2_2") (pintype "input"))
      (node (ref "U6") (pin "17") (pinfunction "CCP_17") (pintype "input"))
    )
    (net (code "29") (name "Net-(U6-D2#)") (class "Default")
      (node (ref "R7") (pin "2") (pinfunction "2_2") (pintype "input"))
      (node (ref "U6") (pin "13") (pinfunction "D2#_13") (pintype "input"))
    )
    (net (code "30") (name "Net-(U7-OSC1)") (class "Default")
      (node (ref "C3") (pin "1") (pinfunction "1_1") (pintype "input"))
      (node (ref "U7") (pin "9") (pinfunction "OSC1_9") (pintype "input"))
      (node (ref "X1") (pin "2") (pinfunction "OSC2_2") (pintype "input"))
    )
    (net (code "31") (name "Net-(U7-OSC2)") (class "Default")
      (node (ref "C2") (pin "1") (pinfunction "1_1") (pintype "input"))
      (node (ref "U7") (pin "8") (pinfunction "OSC2_8") (pintype "input"))
      (node (ref "X1") (pin "1") (pinfunction "OSC1_1") (pintype "input"))
    )
    (net (code "32") (name "Net-(U7-RXCAN)") (class "Default")
      (node (ref "U7") (pin "2") (pinfunction "RXCAN_2") (pintype "input"))
      (node (ref "U8") (pin "4") (pinfunction "RXD_4") (pintype "input"))
    )
    (net (code "33") (name "Net-(U7-TXCAN)") (class "Default")
      (node (ref "U7") (pin "1") (pinfunction "TXCAN_1") (pintype "input"))
      (node (ref "U8") (pin "1") (pinfunction "TXD_1") (pintype "input"))
    )
    (net (code "34") (name "RESET#") (class "Default")
      (node (ref "U1") (pin "28") (pinfunction "RESET_28") (pintype "input"))
      (node (ref "U6") (pin "20") (pinfunction "EN_20") (pintype "input"))
      (node (ref "U7") (pin "19") (pinfunction "RESET#_19") (pintype "input"))
    )
    (net (code "35") (name "TPS1") (class "Default")
      (node (ref "U1") (pin "19") (pinfunction "A0_19") (pintype "input"))
      (node (ref "U3") (pin "5") (pinfunction "5_5") (pintype "input"))
    )
    (net (code "36") (name "TPS2") (class "Default")
      (node (ref "U1") (pin "20") (pinfunction "A1_20") (pintype "input"))
      (node (ref "U3") (pin "6") (pinfunction "6_6") (pintype "input"))
    )
    (net (code "37") (name "WSPEED_IO") (class "Default")
      (node (ref "R5") (pin "1") (pinfunction "1_1") (pintype "input"))
      (node (ref "U1") (pin "5") (pinfunction "D2_5") (pintype "input"))
      (node (ref "U5") (pin "3") (pinfunction "C_3") (pintype "input"))
    )
    (net (code "38") (name "WSPEED_SENSOR") (class "Default")
      (node (ref "R1") (pin "2") (pinfunction "2_2") (pintype "input"))
      (node (ref "R2") (pin "2") (pinfunction "2_2") (pintype "input"))
      (node (ref "U2") (pin "6") (pinfunction "6_6") (pintype "input"))
    )
    (net (code "39") (name "unconnected-(U1-3V3-Pad17)") (class "Default")
      (node (ref "U1") (pin "17") (pinfunction "3V3_17") (pintype "input"))
    )
    (net (code "40") (name "unconnected-(U1-A6-Pad25)") (class "Default")
      (node (ref "U1") (pin "25") (pinfunction "A6_25") (pintype "input"))
    )
    (net (code "41") (name "unconnected-(U1-A7-Pad26)") (class "Default")
      (node (ref "U1") (pin "26") (pinfunction "A7_26") (pintype "input"))
    )
    (net (code "42") (name "unconnected-(U1-AREF-Pad18)") (class "Default")
      (node (ref "U1") (pin "18") (pinfunction "AREF_18") (pintype "input"))
    )
    (net (code "43") (name "unconnected-(U1-D0{slash}RX-Pad2)") (class "Default")
      (node (ref "U1") (pin "2") (pinfunction "D0/RX_2") (pintype "input"))
    )
    (net (code "44") (name "unconnected-(U1-D1{slash}TX-Pad1)") (class "Default")
      (node (ref "U1") (pin "1") (pinfunction "D1/TX_1") (pintype "input"))
    )
    (net (code "45") (name "unconnected-(U1-RESET-Pad3)") (class "Default")
      (node (ref "U1") (pin "3") (pinfunction "RESET_3") (pintype "input"))
    )
    (net (code "46") (name "unconnected-(U2-Pad10)") (class "Default")
      (node (ref "U2") (pin "10") (pinfunction "10_10") (pintype "input"))
    )
    (net (code "47") (name "unconnected-(U7-CLKOUT{slash}SOF-Pad3)") (class "Default")
      (node (ref "U7") (pin "3") (pinfunction "CLKOUT/SOF_3") (pintype "input"))
    )
    (net (code "48") (name "unconnected-(U7-NC-Pad6)") (class "Default")
      (node (ref "U7") (pin "6") (pinfunction "NC_6") (pintype "input"))
    )
    (net (code "49") (name "unconnected-(U7-NC-Pad15)") (class "Default")
      (node (ref "U7") (pin "15") (pinfunction "NC_15") (pintype "input"))
    )
    (net (code "50") (name "unconnected-(U7-RX0BF#-Pad12)") (class "Default")
      (node (ref "U7") (pin "12") (pinfunction "RX0BF#_12") (pintype "input"))
    )
    (net (code "51") (name "unconnected-(U7-RX1BF#-Pad11)") (class "Default")
      (node (ref "U7") (pin "11") (pinfunction "RX1BF#_11") (pintype "input"))
    )
    (net (code "52") (name "unconnected-(U7-TX0RTS#-Pad4)") (class "Default")
      (node (ref "U7") (pin "4") (pinfunction "TX0RTS#_4") (pintype "input"))
    )
    (net (code "53") (name "unconnected-(U7-TX1RTS#-Pad5)") (class "Default")
      (node (ref "U7") (pin "5") (pinfunction "TX1RTS#_5") (pintype "input"))
    )
    (net (code "54") (name "unconnected-(U7-TX2RTS#-Pad7)") (class "Default")
      (node (ref "U7") (pin "7") (pinfunction "TX2RTS#_7") (pintype "input"))
    )
    (net (code "55") (name "unconnected-(U8-VREF-Pad5)") (class "Default")
      (node (ref "U8") (pin "5") (pinfunction "VREF_5") (pintype "input"))
    )
  )
)
